# RS485.net
KiCad netlist of a schematic drawn in Altium Designer
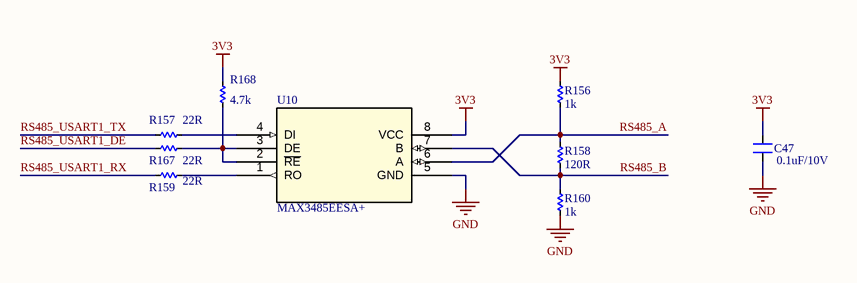
[diagram p0: RS485.SchDoc]

(export (version "E")
  (design (tool "Eeschema 10.0.6"))
  (components
    (comp (ref "C47")
      (value "0.1uF/10V")
      (footprint "CAP_C_1608X80")
      (libsource (lib "EXP_HW_V3") (part "Capacitors"))
    )
    (comp (ref "R156")
      (value "1k")
      (footprint "RES_C_1608X60")
      (description "SMD")
      (fields
        (field (name "MANUFACTURER") "Generic Components")
        (field (name "PUBLISHER") "Altium Hobart Technology Centre")
      )
      (libsource (lib "EXP_HW_V3") (part "Res SMD"))
    )
    (comp (ref "R157")
      (value "22R")
      (footprint "RES_C_1608X60")
      (description "SMD")
      (fields
        (field (name "MANUFACTURER") "Generic Components")
        (field (name "PUBLISHER") "Altium Hobart Technology Centre")
      )
      (libsource (lib "EXP_HW_V3") (part "Res SMD"))
    )
    (comp (ref "R158")
      (value "120R")
      (footprint "RES_C_1608X60")
      (description "SMD")
      (fields
        (field (name "MANUFACTURER") "Generic Components")
        (field (name "PUBLISHER") "Altium Hobart Technology Centre")
      )
      (libsource (lib "EXP_HW_V3") (part "Res SMD"))
    )
    (comp (ref "R159")
      (value "22R")
      (footprint "RES_C_1608X60")
      (description "SMD")
      (fields
        (field (name "MANUFACTURER") "Generic Components")
        (field (name "PUBLISHER") "Altium Hobart Technology Centre")
      )
      (libsource (lib "EXP_HW_V3") (part "Res SMD"))
    )
    (comp (ref "R160")
      (value "1k")
      (footprint "RES_C_1608X60")
      (description "SMD")
      (fields
        (field (name "MANUFACTURER") "Generic Components")
        (field (name "PUBLISHER") "Altium Hobart Technology Centre")
      )
      (libsource (lib "EXP_HW_V3") (part "Res SMD"))
    )
    (comp (ref "R167")
      (value "22R")
      (footprint "RES_C_1608X60")
      (description "SMD")
      (fields
        (field (name "MANUFACTURER") "Generic Components")
        (field (name "PUBLISHER") "Altium Hobart Technology Centre")
      )
      (libsource (lib "EXP_HW_V3") (part "Res SMD"))
    )
    (comp (ref "R168")
      (value "4.7k")
      (footprint "RES_C_1608X60")
      (description "SMD")
      (fields
        (field (name "MANUFACTURER") "Generic Components")
        (field (name "PUBLISHER") "Altium Hobart Technology Centre")
      )
      (libsource (lib "EXP_HW_V3") (part "Res SMD"))
    )
    (comp (ref "U10")
      (value "MAX3485EESA+")
      (footprint "SOIC8_3.9mm")
      (description "IC TRANSCEIVER HALF 1/1 8SOIC")
      (libsource (lib "EXP_HW_V3") (part "MAX3485EESA+"))
    )
  )
  (nets
    (net (code "1") (name "/RS485_A") (class "Default")
      (node (ref "R156") (pin "2") (pinfunction "2_2") (pintype "passive"))
      (node (ref "R158") (pin "1") (pinfunction "1_1") (pintype "passive"))
      (node (ref "U10") (pin "6") (pinfunction "A_6") (pintype "bidirectional"))
    )
    (net (code "2") (name "/RS485_B") (class "Default")
      (node (ref "R158") (pin "2") (pinfunction "2_2") (pintype "passive"))
      (node (ref "R160") (pin "1") (pinfunction "1_1") (pintype "passive"))
      (node (ref "U10") (pin "7") (pinfunction "B_7") (pintype "bidirectional"))
    )
    (net (code "3") (name "/RS485_USART1_DE") (class "Default")
      (node (ref "R167") (pin "2") (pinfunction "2_2") (pintype "passive"))
    )
    (net (code "4") (name "/RS485_USART1_RX") (class "Default")
      (node (ref "R159") (pin "2") (pinfunction "2_2") (pintype "passive"))
    )
    (net (code "5") (name "/RS485_USART1_TX") (class "Default")
      (node (ref "R157") (pin "2") (pinfunction "2_2") (pintype "passive"))
    )
    (net (code "6") (name "3V3") (class "Default")
      (node (ref "C47") (pin "2") (pinfunction "2_2") (pintype "passive"))
      (node (ref "R156") (pin "1") (pinfunction "1_1") (pintype "passive"))
      (node (ref "R168") (pin "1") (pinfunction "1_1") (pintype "passive"))
      (node (ref "U10") (pin "8") (pinfunction "VCC_8") (pintype "passive"))
    )
    (net (code "7") (name "GND") (class "Default")
      (node (ref "C47") (pin "1") (pinfunction "1_1") (pintype "passive"))
      (node (ref "R160") (pin "2") (pinfunction "2_2") (pintype "passive"))
      (node (ref "U10") (pin "5") (pinfunction "GND_5") (pintype "passive"))
    )
    (net (code "8") (name "Net-(U10-DE)") (class "Default")
      (node (ref "R167") (pin "1") (pinfunction "1_1") (pintype "passive"))
      (node (ref "R168") (pin "2") (pinfunction "2_2") (pintype "passive"))
      (node (ref "U10") (pin "2") (pinfunction "~{RE}_2") (pintype "passive"))
      (node (ref "U10") (pin "3") (pinfunction "DE_3") (pintype "passive"))
    )
    (net (code "9") (name "Net-(U10-DI)") (class "Default")
      (node (ref "R157") (pin "1") (pinfunction "1_1") (pintype "passive"))
      (node (ref "U10") (pin "4") (pinfunction "DI_4") (pintype "input"))
    )
    (net (code "10") (name "Net-(U10-RO)") (class "Default")
      (node (ref "R159") (pin "1") (pinfunction "1_1") (pintype "passive"))
      (node (ref "U10") (pin "1") (pinfunction "RO_1") (pintype "output"))
    )
  )
)
